# SCH_Waiduino-NFC-Card-Hack-Club_2024-07-.net
KiCad netlist of a schematic drawn in EasyEDA
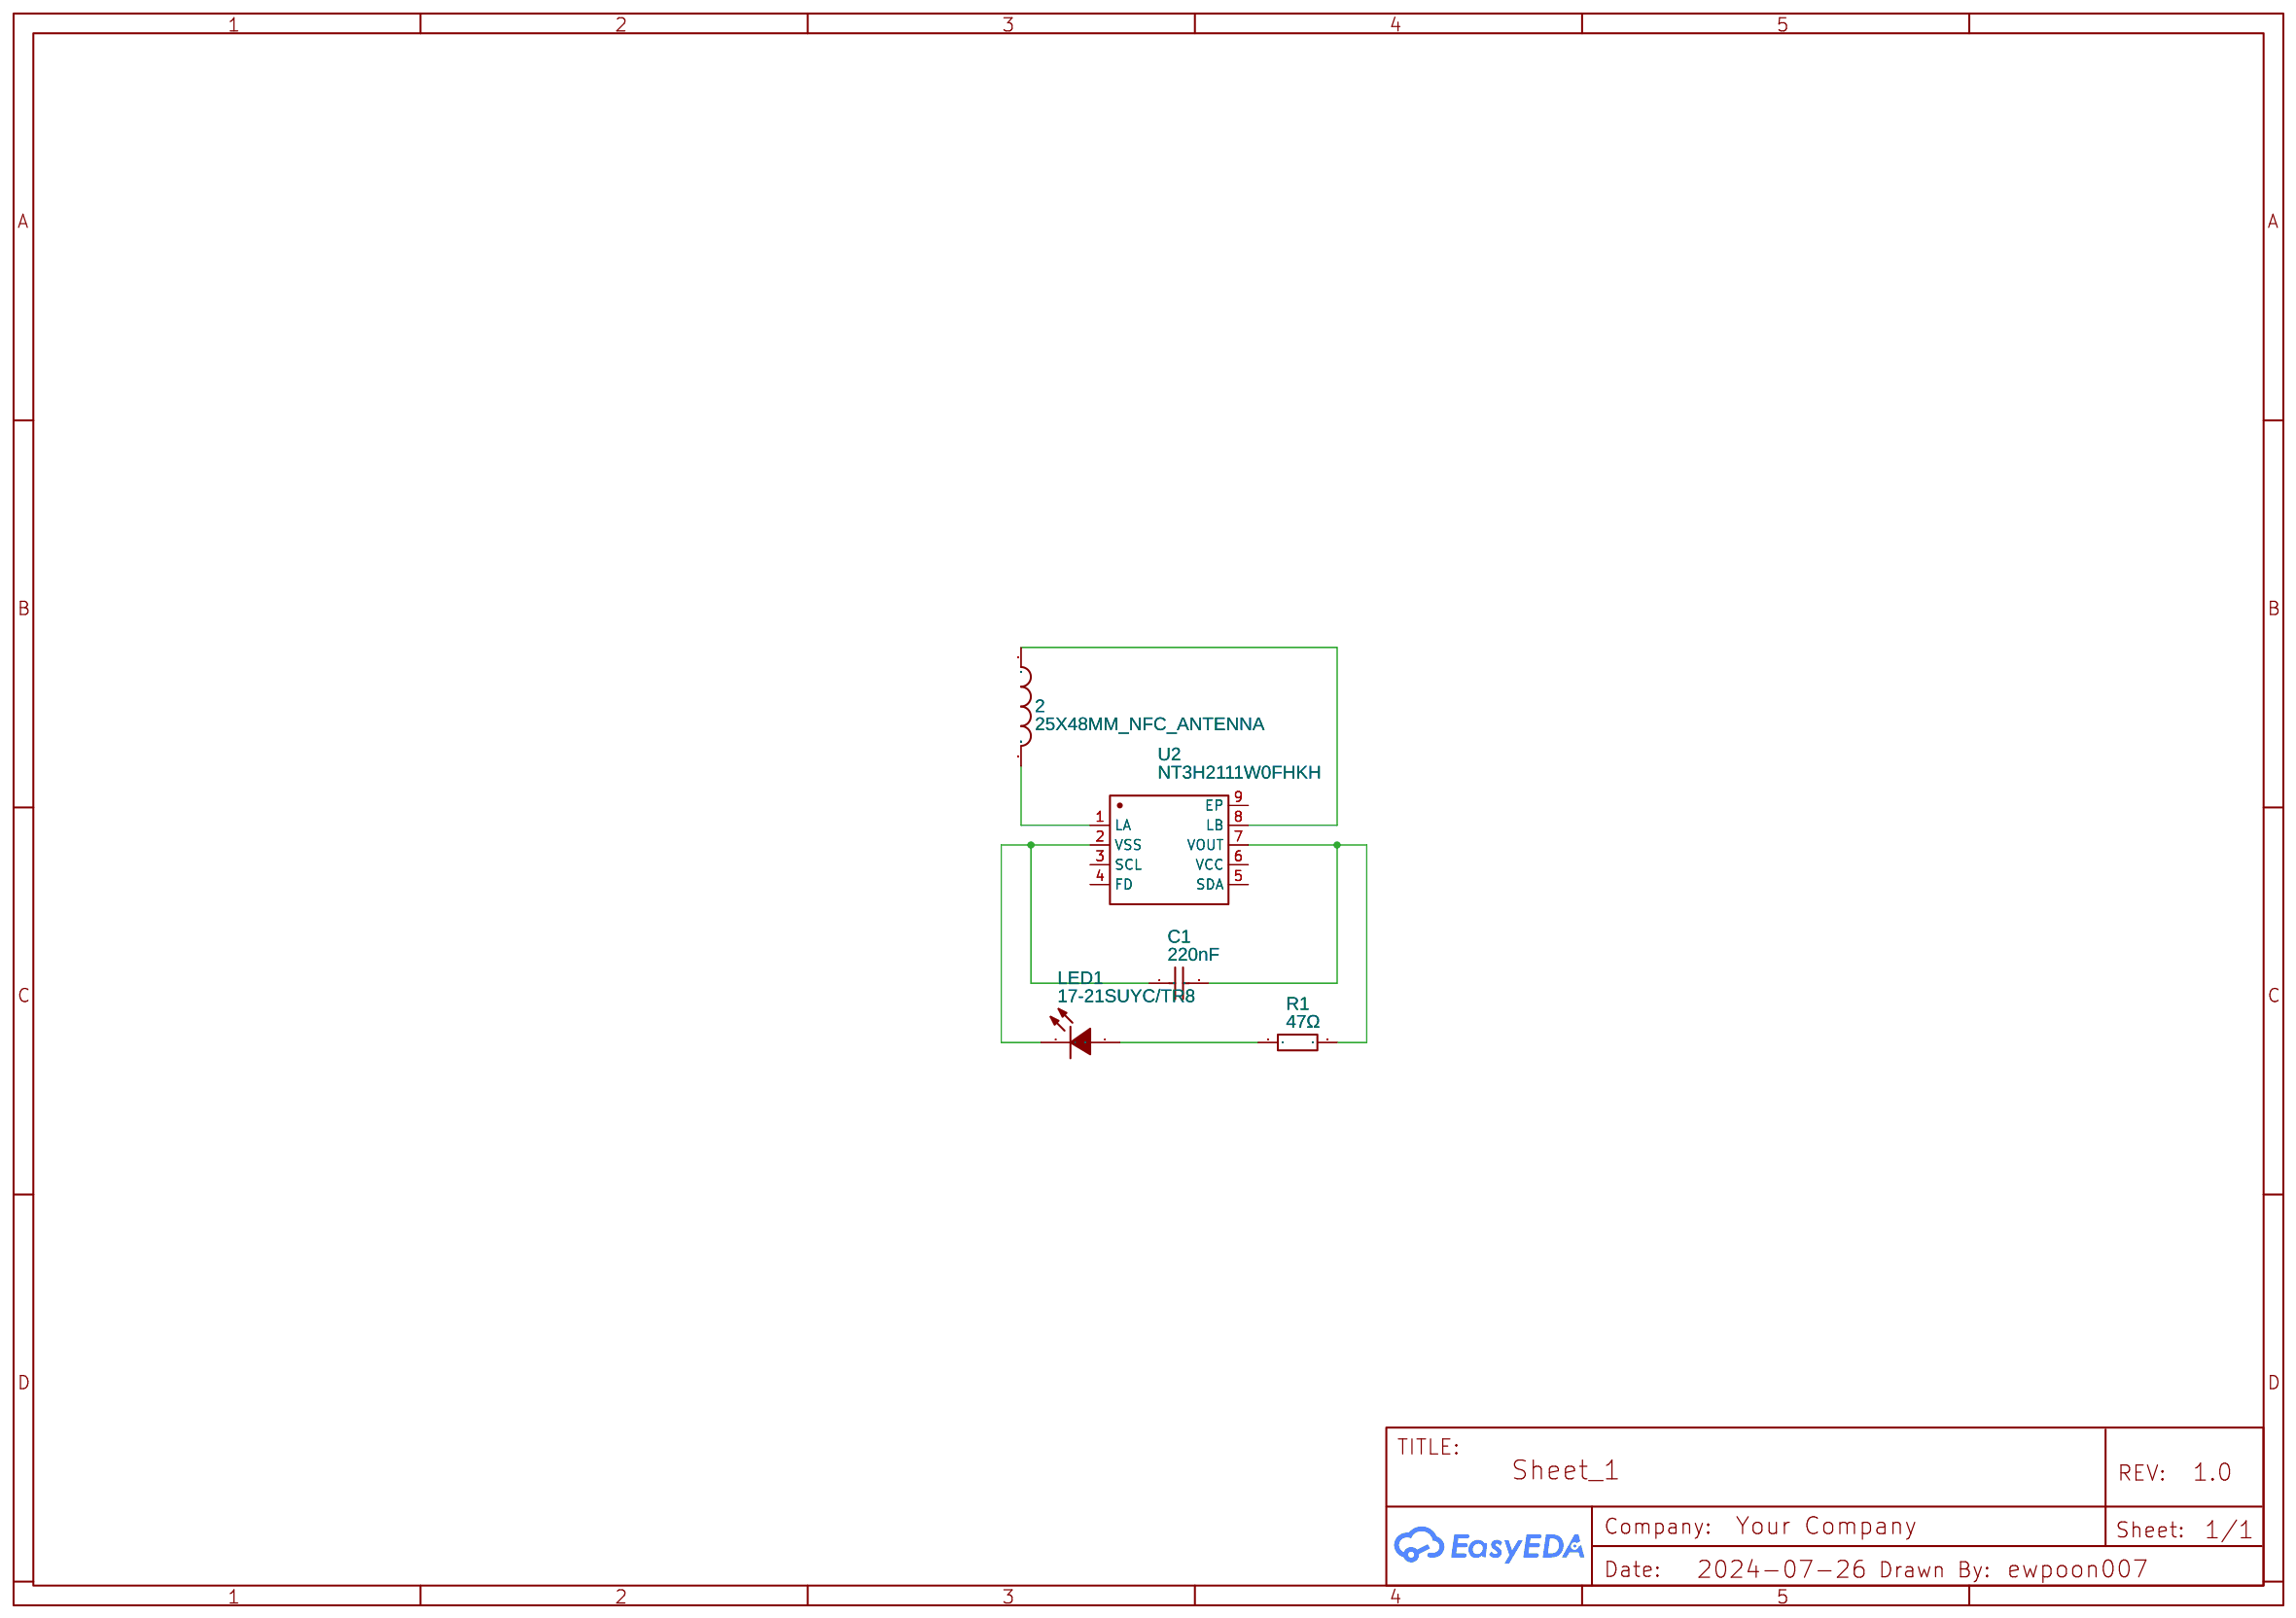
[diagram p0: schematic sheet]

(export (version "E")
  (design (tool "Eeschema 10.0.6"))
  (components
    (comp (ref "2") (value "25X48MM_NFC_ANTENNA") (libsource (lib "") (part "25X48MM_NFC_ANTENNA")))
    (comp (ref "C1")
      (value "220nF")
      (fields
        (field (name "Manufacturer Part") "CL10B224KA8NNNC")
        (field (name "Manufacturer") "SAMSUNG(三星)")
      )
      (libsource (lib "") (part "CL10B224KA8NNNC"))
    )
    (comp (ref "LED1")
      (value "17-21SUYC/TR8")
      (fields (field (name "Manufacturer Part") "KT-0805黄灯") (field (name "Manufacturer") "KENTO"))
      (libsource (lib "") (part "17-21SUYC/TR8"))
    )
    (comp (ref "R1")
      (value "47Ω")
      (fields
        (field (name "Manufacturer Part") "0603WAF470JT5E")
        (field (name "Manufacturer") "UNI-ROYAL(厚声)")
      )
      (libsource (lib "") (part "0603WAF470JT5E"))
    )
    (comp (ref "U2")
      (value "NT3H2111W0FHKH")
      (fields (field (name "Manufacturer") "NXP(恩智浦)"))
      (libsource (lib "") (part "NT3H2111W0FHKH"))
    )
  )
  (nets
    (net (code "1") (name "Net-(LED1-+)") (class "Default")
      (node (ref "LED1") (pin "1") (pinfunction "+_1") (pintype "unspecified"))
      (node (ref "R1") (pin "1") (pinfunction "1_1") (pintype "input"))
    )
    (net (code "2") (name "Net-(LED1--)") (class "Default")
      (node (ref "C1") (pin "1") (pinfunction "1_1") (pintype "input"))
      (node (ref "LED1") (pin "2") (pinfunction "-_2") (pintype "unspecified"))
      (node (ref "U2") (pin "2") (pinfunction "VSS_2") (pintype "unspecified"))
    )
    (net (code "3") (name "Net-(U2-LA)") (class "Default")
      (node (ref "2") (pin "P$2") (pinfunction "P$2_P$2") (pintype "bidirectional"))
      (node (ref "U2") (pin "1") (pinfunction "LA_1") (pintype "unspecified"))
    )
    (net (code "4") (name "Net-(U2-LB)") (class "Default")
      (node (ref "2") (pin "P$1") (pinfunction "P$1_P$1") (pintype "bidirectional"))
      (node (ref "U2") (pin "8") (pinfunction "LB_8") (pintype "unspecified"))
    )
    (net (code "5") (name "Net-(U2-VOUT)") (class "Default")
      (node (ref "C1") (pin "2") (pinfunction "2_2") (pintype "input"))
      (node (ref "R1") (pin "2") (pinfunction "2_2") (pintype "input"))
      (node (ref "U2") (pin "7") (pinfunction "VOUT_7") (pintype "unspecified"))
    )
    (net (code "6") (name "unconnected-(U2-EP-Pad9)") (class "Default")
      (node (ref "U2") (pin "9") (pinfunction "EP_9") (pintype "unspecified"))
    )
    (net (code "7") (name "unconnected-(U2-FD-Pad4)") (class "Default")
      (node (ref "U2") (pin "4") (pinfunction "FD_4") (pintype "unspecified"))
    )
    (net (code "8") (name "unconnected-(U2-SCL-Pad3)") (class "Default")
      (node (ref "U2") (pin "3") (pinfunction "SCL_3") (pintype "unspecified"))
    )
    (net (code "9") (name "unconnected-(U2-SDA-Pad5)") (class "Default")
      (node (ref "U2") (pin "5") (pinfunction "SDA_5") (pintype "unspecified"))
    )
    (net (code "10") (name "unconnected-(U2-VCC-Pad6)") (class "Default")
      (node (ref "U2") (pin "6") (pinfunction "VCC_6") (pintype "unspecified"))
    )
  )
)
